# Power_Stage.net
KiCad netlist of a schematic drawn in Altium Designer
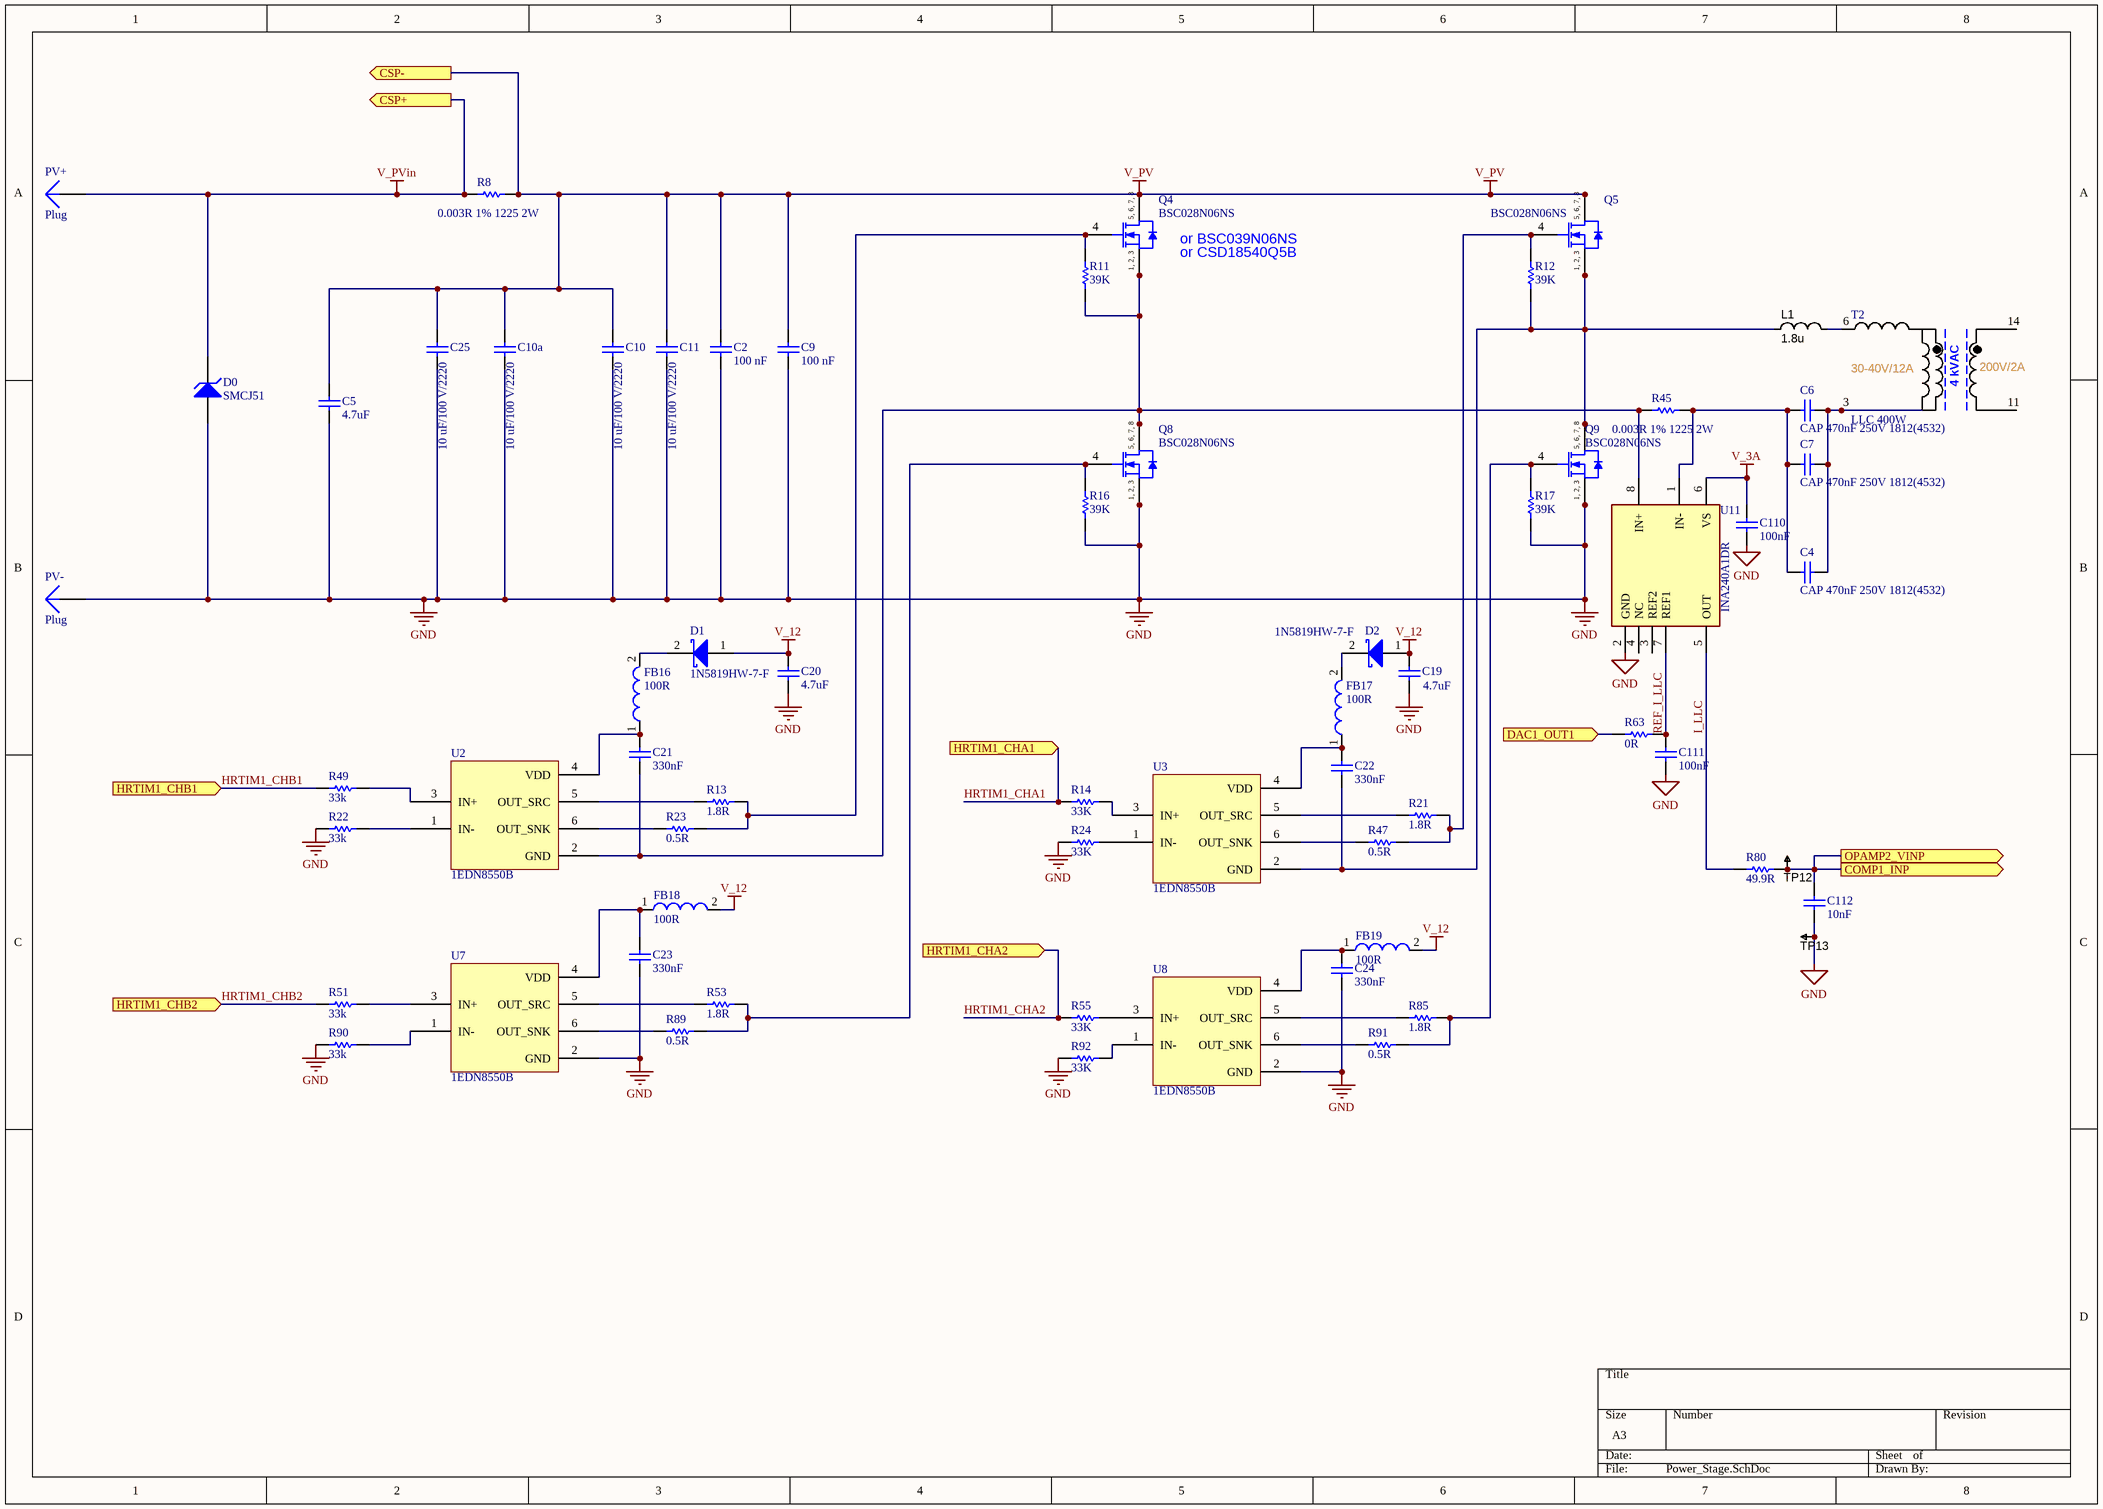
[diagram p0: Power_Stage.SchDoc]

(export (version "E")
  (design (tool "Eeschema 10.0.6"))
  (components
    (comp (ref "C2")
      (value "100 nF")
      (footprint "CAPC2013X94X50NL20T25")
      (description "X7R 100nF ±10% 100V 0805 Multilayer Ceramic Capacitors MLCC - SMD/SMT ROHS")
      (fields
        (field (name "MANUFACTURER") "AVX Interconnect / Elco")
        (field (name "PART NUMBER") "08051C104JAT2A")
      )
      (libsource (lib "Altium Content Vault") (part "CAP"))
    )
    (comp (ref "C4")
      (value "CAP 470nF 250V 1812(4532)")
      (footprint "CAPC1812(4532)190_M")
      (description "CAP 470nF 250V ±10% 1812 (4532 Metric) Thickness 1.9mm SMD")
      (fields (field (name "TOLERANCE") "Â±10%"))
      (libsource (lib "Altium Content Vault") (part "CAP"))
    )
    (comp (ref "C5")
      (value "4.7uF")
      (footprint "CAPC3225X279X50NL20T25")
      (description "Ceramic Capacitor, 100 V, 4.7 uF, +/-10%, -55 to 85 degC, 2-Pin SMD (1210), RoHS, Tape and Reel")
      (fields (field (name "TOLERANCE") "10%") (field (name "MANUFACTURER") "AVX"))
      (libsource (lib "DCDC") (part "CMP-2000-05478-1"))
    )
    (comp (ref "C6")
      (value "CAP 470nF 250V 1812(4532)")
      (footprint "CAPC1812(4532)190_M")
      (description "CAP 470nF 250V ±10% 1812 (4532 Metric) Thickness 1.9mm SMD")
      (fields (field (name "TOLERANCE") "Â±10%"))
      (libsource (lib "Altium Content Vault") (part "CAP"))
    )
    (comp (ref "C7")
      (value "CAP 470nF 250V 1812(4532)")
      (footprint "CAPC1812(4532)190_M")
      (description "CAP 470nF 250V ±10% 1812 (4532 Metric) Thickness 1.9mm SMD")
      (fields (field (name "TOLERANCE") "Â±10%"))
      (libsource (lib "Altium Content Vault") (part "CAP"))
    )
    (comp (ref "C9")
      (value "100 nF")
      (footprint "CAPC2013X94X50NL20T25")
      (description "X7R 100nF ±10% 100V 0805 Multilayer Ceramic Capacitors MLCC - SMD/SMT ROHS")
      (fields
        (field (name "MANUFACTURER") "AVX Interconnect / Elco")
        (field (name "PART NUMBER") "08051C104JAT2A")
      )
      (libsource (lib "Altium Content Vault") (part "CAP"))
    )
    (comp (ref "C10")
      (value "10 uF/100 V/2220")
      (footprint "CAPC5750X279X64LL40T39")
      (description "Chip Capacitor, 10 uF, +/- 20%, 100 V, -55 to 125 degC, 2220 (5750 Metric), RoHS, Tape and Reel")
      (fields (field (name "MANUFACTURER") "AVX") (field (name "MANUFACTURER PART NUMBER") "22201C106MAT2A"))
      (libsource (lib "Altium Content Vault") (part "CAP-NP-2"))
    )
    (comp (ref "C10a")
      (value "10 uF/100 V/2220")
      (footprint "CAPC5750X279X64LL40T39")
      (description "Chip Capacitor, 10 uF, +/- 20%, 100 V, -55 to 125 degC, 2220 (5750 Metric), RoHS, Tape and Reel")
      (fields (field (name "MANUFACTURER") "AVX") (field (name "MANUFACTURER PART NUMBER") "22201C106MAT2A"))
      (libsource (lib "Altium Content Vault") (part "CAP-NP-2"))
    )
    (comp (ref "C11")
      (value "10 uF/100 V/2220")
      (footprint "CAPC5750X279X64LL40T39")
      (description "Chip Capacitor, 10 uF, +/- 20%, 100 V, -55 to 125 degC, 2220 (5750 Metric), RoHS, Tape and Reel")
      (fields (field (name "MANUFACTURER") "AVX") (field (name "MANUFACTURER PART NUMBER") "22201C106MAT2A"))
      (libsource (lib "Altium Content Vault") (part "CAP-NP-2"))
    )
    (comp (ref "C19")
      (value "C1206C105K3RACTU")
      (footprint "CAPC3216X180X50ML20T25")
      (description "X7R ±10% 50V 4.7uF 1206 Multilayer Ceramic Capacitors MLCC - SMD/SMT ROHS")
      (fields
        (field (name "CAPACITANCE") "4.7uF")
        (field (name "MANUFACTURER") "Kemet")
        (field (name "TOLERANCE") "10%")
      )
      (libsource (lib "Altium Content Vault") (part "CAP-NP-2"))
    )
    (comp (ref "C20")
      (value "C1206C105K3RACTU")
      (footprint "CAPC3216X180X50ML20T25")
      (description "X7R ±10% 50V 4.7uF 1206 Multilayer Ceramic Capacitors MLCC - SMD/SMT ROHS")
      (fields
        (field (name "CAPACITANCE") "4.7uF")
        (field (name "MANUFACTURER") "Kemet")
        (field (name "TOLERANCE") "10%")
      )
      (libsource (lib "Altium Content Vault") (part "CAP-NP-2"))
    )
    (comp (ref "C21")
      (value "330nF")
      (footprint "CAPC2013X135X45ML10T25")
      (description "X7R ±10% 50V 330nF 0805 Multilayer Ceramic Capacitors MLCC - SMD/SMT ROHS")
      (fields (field (name "VOLTAGE") "50V") (field (name "TOLERANCE") "10%"))
      (libsource (lib "Altium Content Vault") (part "CAP-NP-2"))
    )
    (comp (ref "C22")
      (value "330nF")
      (footprint "CAPC2013X135X45ML10T25")
      (description "X7R ±10% 50V 330nF 0805 Multilayer Ceramic Capacitors MLCC - SMD/SMT ROHS")
      (fields (field (name "VOLTAGE") "50V") (field (name "TOLERANCE") "10%"))
      (libsource (lib "Altium Content Vault") (part "CAP-NP-2"))
    )
    (comp (ref "C23")
      (value "330nF")
      (footprint "CAPC2013X135X45ML10T25")
      (description "X7R ±10% 50V 330nF 0805 Multilayer Ceramic Capacitors MLCC - SMD/SMT ROHS")
      (fields (field (name "VOLTAGE") "50V") (field (name "TOLERANCE") "10%"))
      (libsource (lib "Altium Content Vault") (part "CAP-NP-2"))
    )
    (comp (ref "C24")
      (value "330nF")
      (footprint "CAPC2013X135X45ML10T25")
      (description "X7R ±10% 50V 330nF 0805 Multilayer Ceramic Capacitors MLCC - SMD/SMT ROHS")
      (fields (field (name "VOLTAGE") "50V") (field (name "TOLERANCE") "10%"))
      (libsource (lib "Altium Content Vault") (part "CAP-NP-2"))
    )
    (comp (ref "C25")
      (value "10 uF/100 V/2220")
      (footprint "CAPC5750X279X64LL40T39")
      (description "Chip Capacitor, 10 uF, +/- 20%, 100 V, -55 to 125 degC, 2220 (5750 Metric), RoHS, Tape and Reel")
      (fields (field (name "MANUFACTURER") "AVX") (field (name "MANUFACTURER PART NUMBER") "22201C106MAT2A"))
      (libsource (lib "Altium Content Vault") (part "CAP-NP-2"))
    )
    (comp (ref "C110")
      (value "100nF")
      (footprint "CAPC1608X90X35NL10T15")
      (description "X7R 100nF ±10% 50V 0603 Multilayer Ceramic Capacitors MLCC - SMD/SMT ROHS")
      (fields (field (name "PART NUMBER") "GCM188R72A104KA64D") (field (name "MANUFACTURER") "Murata"))
      (libsource (lib "DCDC") (part "CAP"))
    )
    (comp (ref "C111")
      (value "100nF")
      (footprint "CAPC1608X90X35NL10T15")
      (description "X7R 100nF ±10% 50V 0603 Multilayer Ceramic Capacitors MLCC - SMD/SMT ROHS")
      (fields (field (name "PART NUMBER") "GCM188R72A104KA64D") (field (name "MANUFACTURER") "Murata"))
      (libsource (lib "DCDC") (part "CAP"))
    )
    (comp (ref "C112")
      (value "10nF")
      (footprint "CAPC1005X56X25NL10T15")
      (description "X7R ±10% 50V 10nF 0603 Multilayer Ceramic Capacitors MLCC - SMD/SMT ROHS")
      (fields
        (field (name "MANUFACTURER") "AVX Interconnect / Elco")
        (field (name "PART NUMBER") "04023C103JAT2A")
      )
      (libsource (lib "DCDC") (part "CAP"))
    )
    (comp (ref "D0")
      (value "SMCJ51")
      (footprint "FAIR-DO-214AB-2_V")
      (description "Transient Voltage Suppressor, 1500 W, 36 V, 2-Pin SMD, RoHS, Tape and Reel")
      (fields (field (name "MANUFACTURER") "Fairchild Semiconductor"))
      (libsource (lib "Altium Content Vault") (part "DZEN-AK-2"))
    )
    (comp (ref "D1")
      (value "1N5819HW-7-F")
      (footprint "DIOD-SOD-123-2_V")
      (fields (field (name "MANUFACTURER") "Diodes Inc") (field (name "JLCPCB PART #") "C8598"))
      (libsource (lib "Altium Content Vault") (part "DIOD-DSKY-A1K2-2"))
    )
    (comp (ref "D2")
      (value "1N5819HW-7-F")
      (footprint "DIOD-SOD-123-2_V")
      (fields (field (name "MANUFACTURER") "Diodes Inc") (field (name "JLCPCB PART #") "C8598"))
      (libsource (lib "Altium Content Vault") (part "DIOD-DSKY-A1K2-2"))
    )
    (comp (ref "FB16")
      (value "100R")
      (footprint "SMD-0603")
      (description "SMD EMI Suppression Ferrite Bead WE-CBF, Z = 1500 Ohm")
      (libsource (lib "Altium Content Vault") (part "PAS-IND-INDUCTOR-2"))
    )
    (comp (ref "FB17")
      (value "100R")
      (footprint "SMD-0603")
      (description "SMD EMI Suppression Ferrite Bead WE-CBF, Z = 1500 Ohm")
      (libsource (lib "Altium Content Vault") (part "PAS-IND-INDUCTOR-2"))
    )
    (comp (ref "FB18")
      (value "100R")
      (footprint "SMD-0603")
      (description "SMD EMI Suppression Ferrite Bead WE-CBF, Z = 1500 Ohm")
      (libsource (lib "Altium Content Vault") (part "PAS-IND-INDUCTOR-2"))
    )
    (comp (ref "FB19")
      (value "100R")
      (footprint "SMD-0603")
      (description "SMD EMI Suppression Ferrite Bead WE-CBF, Z = 1500 Ohm")
      (libsource (lib "Altium Content Vault") (part "PAS-IND-INDUCTOR-2"))
    )
    (comp (ref "L1")
      (value "1.8u")
      (footprint "IND LLC")
      (description "Inductor SMD chip 150nH 1008")
      (fields (field (name "TOLERANCE") "±5%"))
      (libsource (lib "PBL - Inductors") (part "INDC_150n_1008"))
    )
    (comp (ref "PV+")
      (value "Plug")
      (footprint "PV_PAD")
      (fields (field (name "PUBLISHER") "Altium Limited"))
      (libsource (lib "Miscellaneous Connectors") (part "Plug"))
    )
    (comp (ref "PV-")
      (value "Plug")
      (footprint "PV_PAD")
      (fields (field (name "PUBLISHER") "Altium Limited"))
      (libsource (lib "Miscellaneous Connectors") (part "Plug"))
    )
    (comp (ref "Q4")
      (value "BSC028N06NS")
      (footprint "INF-PG-TDSON-8-1_V")
      (description "N-Channel OptiMOS Power-Transistor, 60 V VDS, 100 A ID, -55 to 150 degC, PG-TDSON-8-1, Reel, Green")
      (fields (field (name "PARTNUMBER") "BSC027N06LS5") (field (name "MANUFACTURER") "Infineon"))
      (libsource (lib "Altium Content Vault") (part "INF-NEMOS-SSSGDDDD-8"))
    )
    (comp (ref "Q5")
      (value "BSC028N06NS")
      (footprint "INF-PG-TDSON-8-1_V")
      (description "N-Channel OptiMOS Power-Transistor, 60 V VDS, 100 A ID, -55 to 150 degC, PG-TDSON-8-1, Reel, Green")
      (fields (field (name "PARTNUMBER") "BSC027N06LS5") (field (name "MANUFACTURER") "Infineon"))
      (libsource (lib "Altium Content Vault") (part "INF-NEMOS-SSSGDDDD-8"))
    )
    (comp (ref "Q8")
      (value "BSC028N06NS")
      (footprint "INF-PG-TDSON-8-1_V")
      (description "N-Channel OptiMOS Power-Transistor, 60 V VDS, 100 A ID, -55 to 150 degC, PG-TDSON-8-1, Reel, Green")
      (fields (field (name "PARTNUMBER") "BSC027N06LS5") (field (name "MANUFACTURER") "Infineon"))
      (libsource (lib "Altium Content Vault") (part "INF-NEMOS-SSSGDDDD-8"))
    )
    (comp (ref "Q9")
      (value "BSC028N06NS")
      (footprint "INF-PG-TDSON-8-1_V")
      (description "N-Channel OptiMOS Power-Transistor, 60 V VDS, 100 A ID, -55 to 150 degC, PG-TDSON-8-1, Reel, Green")
      (fields (field (name "PARTNUMBER") "BSC027N06LS5") (field (name "MANUFACTURER") "Infineon"))
      (libsource (lib "Altium Content Vault") (part "INF-NEMOS-SSSGDDDD-8"))
    )
    (comp (ref "R8")
      (value "0.003R 1% 1225 2W")
      (footprint "RESC3264X06N")
      (description "RES SMD 3 MOHM 3W 2512 WIDE")
      (fields
        (field (name "MANUFACTURER") "Susumu")
        (field (name "MANUFACTURER PART NUMBER") "KRL6432E-M-R003-F-T1")
      )
      (libsource (lib "Miscellaneous Devices") (part "RES"))
    )
    (comp (ref "R11")
      (value "39K")
      (footprint "RESC1608X55X30NL20T10")
      (description "±1% 39kΩ ±100ppm/℃ 0.1W 0603 Chip Resistor - Surface Mount ROHS")
      (fields (field (name "PART NUMBER") "RK73B1JTTD103J") (field (name "MANUFACTURER") "KOA Speer"))
      (libsource (lib "Altium Content Vault") (part "RES"))
    )
    (comp (ref "R12")
      (value "39K")
      (footprint "RESC1608X55X30NL20T10")
      (description "±1% 39kΩ ±100ppm/℃ 0.1W 0603 Chip Resistor - Surface Mount ROHS")
      (fields (field (name "PART NUMBER") "RK73B1JTTD103J") (field (name "MANUFACTURER") "KOA Speer"))
      (libsource (lib "Altium Content Vault") (part "RES"))
    )
    (comp (ref "R13")
      (value "1.8R")
      (footprint "RESC3216X70X40ML20T20")
      (fields (field (name "MANUFACTURER") "KOA Speer") (field (name "PART NUMBER") "RK73B2BTTD4R7J"))
      (libsource (lib "Altium Content Vault") (part "RES"))
    )
    (comp (ref "R14")
      (value "33K")
      (footprint "RESC1608X55X25ML10T15")
      (description "Chip Resistor, 100 Ohm, +/- 1%, 0.1 W, -55 to 155 degC, 0603 (1608 Metric), RoHS, Tape and Reel")
      (fields (field (name "TOLERANCE") "1%") (field (name "MANUFACTURER") "Yageo"))
      (libsource (lib "Altium Content Vault") (part "RES-2"))
    )
    (comp (ref "R16")
      (value "39K")
      (footprint "RESC1608X55X30NL20T10")
      (description "±1% 39kΩ ±100ppm/℃ 0.1W 0603 Chip Resistor - Surface Mount ROHS")
      (fields (field (name "PART NUMBER") "RK73B1JTTD103J") (field (name "MANUFACTURER") "KOA Speer"))
      (libsource (lib "Altium Content Vault") (part "RES"))
    )
    (comp (ref "R17")
      (value "39K")
      (footprint "RESC1608X55X30NL20T10")
      (description "±1% 39kΩ ±100ppm/℃ 0.1W 0603 Chip Resistor - Surface Mount ROHS")
      (fields (field (name "PART NUMBER") "RK73B1JTTD103J") (field (name "MANUFACTURER") "KOA Speer"))
      (libsource (lib "Altium Content Vault") (part "RES"))
    )
    (comp (ref "R21")
      (value "1.8R")
      (footprint "RESC3216X70X40ML20T20")
      (fields (field (name "MANUFACTURER") "KOA Speer") (field (name "PART NUMBER") "RK73B2BTTD4R7J"))
      (libsource (lib "Altium Content Vault") (part "RES"))
    )
    (comp (ref "R22")
      (value "33k")
      (footprint "RESC1608X55X25ML10T15")
      (description "Chip Resistor, 100 Ohm, +/- 1%, 0.1 W, -55 to 155 degC, 0603 (1608 Metric), RoHS, Tape and Reel")
      (fields (field (name "TOLERANCE") "1%") (field (name "MANUFACTURER") "Yageo"))
      (libsource (lib "Altium Content Vault") (part "RES-2"))
    )
    (comp (ref "R23")
      (value "0.5R")
      (footprint "RESC3216X70X40ML20T20")
      (fields (field (name "MANUFACTURER") "KOA Speer") (field (name "PART NUMBER") "RK73B2BTTD4R7J"))
      (libsource (lib "Altium Content Vault") (part "RES"))
    )
    (comp (ref "R24")
      (value "33K")
      (footprint "RESC1608X55X25ML10T15")
      (description "Chip Resistor, 100 Ohm, +/- 1%, 0.1 W, -55 to 155 degC, 0603 (1608 Metric), RoHS, Tape and Reel")
      (fields (field (name "TOLERANCE") "1%") (field (name "MANUFACTURER") "Yageo"))
      (libsource (lib "Altium Content Vault") (part "RES-2"))
    )
    (comp (ref "R45")
      (value "0.003R 1% 1225 2W")
      (footprint "RESC3264X06N")
      (description "RES SMD 3 MOHM 3W 2512 WIDE")
      (fields
        (field (name "MANUFACTURER") "Susumu")
        (field (name "MANUFACTURER PART NUMBER") "KRL6432E-M-R003-F-T1")
      )
      (libsource (lib "Miscellaneous Devices") (part "RES"))
    )
    (comp (ref "R47")
      (value "0.5R")
      (footprint "RESC3216X70X40ML20T20")
      (fields (field (name "MANUFACTURER") "KOA Speer") (field (name "PART NUMBER") "RK73B2BTTD4R7J"))
      (libsource (lib "Altium Content Vault") (part "RES"))
    )
    (comp (ref "R49")
      (value "33k")
      (footprint "RESC1608X55X25ML10T15")
      (description "Chip Resistor, 100 Ohm, +/- 1%, 0.1 W, -55 to 155 degC, 0603 (1608 Metric), RoHS, Tape and Reel")
      (fields (field (name "TOLERANCE") "1%") (field (name "MANUFACTURER") "Yageo"))
      (libsource (lib "Altium Content Vault") (part "RES-2"))
    )
    (comp (ref "R51")
      (value "33k")
      (footprint "RESC1608X55X25ML10T15")
      (description "Chip Resistor, 100 Ohm, +/- 1%, 0.1 W, -55 to 155 degC, 0603 (1608 Metric), RoHS, Tape and Reel")
      (fields (field (name "TOLERANCE") "1%") (field (name "MANUFACTURER") "Yageo"))
      (libsource (lib "Altium Content Vault") (part "RES-2"))
    )
    (comp (ref "R53")
      (value "1.8R")
      (footprint "RESC3216X70X40ML20T20")
      (fields (field (name "MANUFACTURER") "KOA Speer") (field (name "PART NUMBER") "RK73B2BTTD4R7J"))
      (libsource (lib "Altium Content Vault") (part "RES"))
    )
    (comp (ref "R55")
      (value "33K")
      (footprint "RESC1608X55X25ML10T15")
      (description "Chip Resistor, 100 Ohm, +/- 1%, 0.1 W, -55 to 155 degC, 0603 (1608 Metric), RoHS, Tape and Reel")
      (fields (field (name "TOLERANCE") "1%") (field (name "MANUFACTURER") "Yageo"))
      (libsource (lib "Altium Content Vault") (part "RES-2"))
    )
    (comp (ref "R63")
      (value "0R")
      (footprint "RESC1608X55X25ML10T15")
      (description "±1% 0Ω 0.1W 0603 Chip Resistor - Surface Mount ROHS")
      (fields (field (name "TOLERANCE") "5%") (field (name "MANUFACTURER") "Yageo"))
      (libsource (lib "Altium Content Vault") (part "RES-2"))
    )
    (comp (ref "R80")
      (value "49.9R")
      (footprint "RESC1608X55X30ML15T15")
      (description "±1% ±200ppm/℃ 0.1W 49.9Ω 0603 Chip Resistor - Surface Mount ROHS")
      (fields (field (name "MANUFACTURER") "Panasonic") (field (name "PART NUMBER") "ERJ-3EKF49R9V"))
      (libsource (lib "Altium Content Vault") (part "RES"))
    )
    (comp (ref "R85")
      (value "1.8R")
      (footprint "RESC3216X70X40ML20T20")
      (fields (field (name "MANUFACTURER") "KOA Speer") (field (name "PART NUMBER") "RK73B2BTTD4R7J"))
      (libsource (lib "Altium Content Vault") (part "RES"))
    )
    (comp (ref "R89")
      (value "0.5R")
      (footprint "RESC3216X70X40ML20T20")
      (fields (field (name "MANUFACTURER") "KOA Speer") (field (name "PART NUMBER") "RK73B2BTTD4R7J"))
      (libsource (lib "Altium Content Vault") (part "RES"))
    )
    (comp (ref "R90")
      (value "33k")
      (footprint "RESC1608X55X25ML10T15")
      (description "Chip Resistor, 100 Ohm, +/- 1%, 0.1 W, -55 to 155 degC, 0603 (1608 Metric), RoHS, Tape and Reel")
      (fields (field (name "TOLERANCE") "1%") (field (name "MANUFACTURER") "Yageo"))
      (libsource (lib "Altium Content Vault") (part "RES-2"))
    )
    (comp (ref "R91")
      (value "0.5R")
      (footprint "RESC3216X70X40ML20T20")
      (fields (field (name "MANUFACTURER") "KOA Speer") (field (name "PART NUMBER") "RK73B2BTTD4R7J"))
      (libsource (lib "Altium Content Vault") (part "RES"))
    )
    (comp (ref "R92")
      (value "33K")
      (footprint "RESC1608X55X25ML10T15")
      (description "Chip Resistor, 100 Ohm, +/- 1%, 0.1 W, -55 to 155 degC, 0603 (1608 Metric), RoHS, Tape and Reel")
      (fields (field (name "TOLERANCE") "1%") (field (name "MANUFACTURER") "Yageo"))
      (libsource (lib "Altium Content Vault") (part "RES-2"))
    )
    (comp (ref "T2")
      (value "LLC 400W")
      (footprint "ETD39-K-V-16P-HORIZONTAL-PRI")
      (description "Lr=1.9uH\r\nLm=10.2uH\r\nn=5.7\r\nVin=30-40V\r\nVout=200V")
      (libsource (lib "TI-ETD39-200V-2A-LLC") (part "TI-ETD39-200V-2A-LLC"))
    )
    (comp (ref "TP12")
      (value "TESTPOINT")
      (footprint "TP-R60")
      (description "SMD test pin")
      (libsource (lib "PBL - Test Points") (part "TESTPOINT"))
    )
    (comp (ref "TP13")
      (value "TESTPOINT")
      (footprint "TP-R60")
      (description "SMD test pin")
      (libsource (lib "PBL - Test Points") (part "TESTPOINT"))
    )
    (comp (ref "U2")
      (value "1EDN8550B")
      (footprint "SOT23-6")
      (description "Single-channel EiceDRIVER™ with true  differential inputs")
      (libsource (lib "1EDN8550B") (part "1EDN8550B"))
    )
    (comp (ref "U3")
      (value "1EDN8550B")
      (footprint "SOT23-6")
      (description "Single-channel EiceDRIVER™ with true  differential inputs")
      (libsource (lib "1EDN8550B") (part "1EDN8550B"))
    )
    (comp (ref "U7")
      (value "1EDN8550B")
      (footprint "SOT23-6")
      (description "Single-channel EiceDRIVER™ with true  differential inputs")
      (libsource (lib "1EDN8550B") (part "1EDN8550B"))
    )
    (comp (ref "U8")
      (value "1EDN8550B")
      (footprint "SOT23-6")
      (description "Single-channel EiceDRIVER™ with true  differential inputs")
      (libsource (lib "1EDN8550B") (part "1EDN8550B"))
    )
    (comp (ref "U11")
      (value "INA240A1DR")
      (footprint "SOIC127P600X175-8AN")
      (description "IC CURR SENSE 1 CIRCUIT 8SOIC")
      (libsource (lib "PBL - Integrated Circuits") (part "a9db4a8a3d73c22b64f8e8a0c239388"))
    )
  )
  (nets
    (net (code "1") (name "/COMP1_INP") (class "Default")
      (node (ref "C112") (pin "2") (pinfunction "2_2") (pintype "passive"))
      (node (ref "R80") (pin "2") (pinfunction "2_2") (pintype "passive"))
      (node (ref "TP12") (pin "1") (pintype "passive"))
    )
    (net (code "2") (name "/DAC1_OUT1") (class "Default")
      (node (ref "R63") (pin "1") (pinfunction "1_1") (pintype "passive"))
    )
    (net (code "3") (name "/HRTIM1_CHA1") (class "Default")
      (node (ref "R14") (pin "1") (pinfunction "1_1") (pintype "passive"))
    )
    (net (code "4") (name "/HRTIM1_CHA2") (class "Default")
      (node (ref "R55") (pin "1") (pinfunction "1_1") (pintype "passive"))
    )
    (net (code "5") (name "/HRTIM1_CHB1") (class "Default")
      (node (ref "R49") (pin "1") (pinfunction "1_1") (pintype "passive"))
    )
    (net (code "6") (name "/HRTIM1_CHB2") (class "Default")
      (node (ref "R51") (pin "1") (pinfunction "1_1") (pintype "passive"))
    )
    (net (code "7") (name "/I_LLC") (class "Default")
      (node (ref "R80") (pin "1") (pinfunction "1_1") (pintype "passive"))
      (node (ref "U11") (pin "5") (pinfunction "OUT_5") (pintype "passive"))
    )
    (net (code "8") (name "/REF_I_LLC") (class "Default")
      (node (ref "C111") (pin "2") (pinfunction "2_2") (pintype "passive"))
      (node (ref "R63") (pin "2") (pinfunction "2_2") (pintype "passive"))
      (node (ref "U11") (pin "7") (pinfunction "REF1_7") (pintype "passive"))
    )
    (net (code "9") (name "GND") (class "Default")
      (node (ref "C10") (pin "1") (pinfunction "1_1") (pintype "passive"))
      (node (ref "C10a") (pin "1") (pinfunction "1_1") (pintype "passive"))
      (node (ref "C11") (pin "1") (pinfunction "1_1") (pintype "passive"))
      (node (ref "C110") (pin "1") (pinfunction "1_1") (pintype "passive"))
      (node (ref "C111") (pin "1") (pinfunction "1_1") (pintype "passive"))
      (node (ref "C112") (pin "1") (pinfunction "1_1") (pintype "passive"))
      (node (ref "C19") (pin "1") (pinfunction "1_1") (pintype "passive"))
      (node (ref "C2") (pin "1") (pinfunction "1_1") (pintype "passive"))
      (node (ref "C20") (pin "1") (pinfunction "1_1") (pintype "passive"))
      (node (ref "C23") (pin "1") (pinfunction "1_1") (pintype "passive"))
      (node (ref "C24") (pin "1") (pinfunction "1_1") (pintype "passive"))
      (node (ref "C25") (pin "1") (pinfunction "1_1") (pintype "passive"))
      (node (ref "C5") (pin "1") (pinfunction "1_1") (pintype "passive"))
      (node (ref "C9") (pin "1") (pinfunction "1_1") (pintype "passive"))
      (node (ref "D0") (pin "1") (pinfunction "A_1") (pintype "passive"))
      (node (ref "PV-") (pin "1") (pinfunction "1_1") (pintype "passive"))
      (node (ref "Q8") (pin "1") (pinfunction "SOURCE_1") (pintype "passive"))
      (node (ref "Q8") (pin "2") (pinfunction "SOURCE_2") (pintype "passive"))
      (node (ref "Q8") (pin "3") (pinfunction "SOURCE_3") (pintype "passive"))
      (node (ref "Q9") (pin "1") (pinfunction "SOURCE_1") (pintype "passive"))
      (node (ref "Q9") (pin "2") (pinfunction "SOURCE_2") (pintype "passive"))
      (node (ref "Q9") (pin "3") (pinfunction "SOURCE_3") (pintype "passive"))
      (node (ref "R16") (pin "1") (pinfunction "1_1") (pintype "passive"))
      (node (ref "R17") (pin "1") (pinfunction "1_1") (pintype "passive"))
      (node (ref "R22") (pin "1") (pinfunction "1_1") (pintype "passive"))
      (node (ref "R24") (pin "1") (pinfunction "1_1") (pintype "passive"))
      (node (ref "R90") (pin "1") (pinfunction "1_1") (pintype "passive"))
      (node (ref "R92") (pin "1") (pinfunction "1_1") (pintype "passive"))
      (node (ref "TP13") (pin "1") (pintype "passive"))
      (node (ref "U11") (pin "2") (pinfunction "GND_2") (pintype "power_in"))
      (node (ref "U7") (pin "2") (pinfunction "GND_2") (pintype "passive"))
      (node (ref "U8") (pin "2") (pinfunction "GND_2") (pintype "passive"))
    )
    (net (code "10") (name "Net-(C4-Pad2)") (class "Default")
      (node (ref "C4") (pin "2") (pinfunction "2_2") (pintype "passive"))
      (node (ref "C6") (pin "2") (pinfunction "2_2") (pintype "passive"))
      (node (ref "C7") (pin "2") (pinfunction "2_2") (pintype "passive"))
      (node (ref "T2") (pin "3") (pinfunction "3_3") (pintype "passive"))
    )
    (net (code "11") (name "Net-(D1-K)") (class "Default")
      (node (ref "D1") (pin "2") (pinfunction "K_2") (pintype "passive"))
      (node (ref "FB16") (pin "2") (pinfunction "2_2") (pintype "passive"))
    )
    (net (code "12") (name "Net-(D2-K)") (class "Default")
      (node (ref "D2") (pin "2") (pinfunction "K_2") (pintype "passive"))
      (node (ref "FB17") (pin "2") (pinfunction "2_2") (pintype "passive"))
    )
    (net (code "13") (name "Net-(L1-Pad2)") (class "Default")
      (node (ref "L1") (pin "2") (pinfunction "2_2") (pintype "passive"))
      (node (ref "T2") (pin "6") (pinfunction "6_6") (pintype "passive"))
    )
    (net (code "14") (name "Net-(Q4-GATE)") (class "Default")
      (node (ref "Q4") (pin "4") (pinfunction "GATE_4") (pintype "passive"))
      (node (ref "R11") (pin "2") (pinfunction "2_2") (pintype "passive"))
      (node (ref "R13") (pin "2") (pinfunction "2_2") (pintype "passive"))
      (node (ref "R23") (pin "2") (pinfunction "2_2") (pintype "passive"))
    )
    (net (code "15") (name "Net-(Q5-GATE)") (class "Default")
      (node (ref "Q5") (pin "4") (pinfunction "GATE_4") (pintype "passive"))
      (node (ref "R12") (pin "2") (pinfunction "2_2") (pintype "passive"))
      (node (ref "R21") (pin "2") (pinfunction "2_2") (pintype "passive"))
      (node (ref "R47") (pin "2") (pinfunction "2_2") (pintype "passive"))
    )
    (net (code "16") (name "Net-(Q8-GATE)") (class "Default")
      (node (ref "Q8") (pin "4") (pinfunction "GATE_4") (pintype "passive"))
      (node (ref "R16") (pin "2") (pinfunction "2_2") (pintype "passive"))
      (node (ref "R53") (pin "2") (pinfunction "2_2") (pintype "passive"))
      (node (ref "R89") (pin "2") (pinfunction "2_2") (pintype "passive"))
    )
    (net (code "17") (name "Net-(Q9-GATE)") (class "Default")
      (node (ref "Q9") (pin "4") (pinfunction "GATE_4") (pintype "passive"))
      (node (ref "R17") (pin "2") (pinfunction "2_2") (pintype "passive"))
      (node (ref "R85") (pin "2") (pinfunction "2_2") (pintype "passive"))
      (node (ref "R91") (pin "2") (pinfunction "2_2") (pintype "passive"))
    )
    (net (code "18") (name "Net-(U2-IN+)") (class "Default")
      (node (ref "R49") (pin "2") (pinfunction "2_2") (pintype "passive"))
      (node (ref "U2") (pin "3") (pinfunction "IN+_3") (pintype "passive"))
    )
    (net (code "19") (name "Net-(U2-IN-)") (class "Default")
      (node (ref "R22") (pin "2") (pinfunction "2_2") (pintype "passive"))
      (node (ref "U2") (pin "1") (pinfunction "IN-_1") (pintype "passive"))
    )
    (net (code "20") (name "Net-(U2-OUT_SNK)") (class "Default")
      (node (ref "R23") (pin "1") (pinfunction "1_1") (pintype "passive"))
      (node (ref "U2") (pin "6") (pinfunction "OUT_SNK_6") (pintype "passive"))
    )
    (net (code "21") (name "Net-(U2-OUT_SRC)") (class "Default")
      (node (ref "R13") (pin "1") (pinfunction "1_1") (pintype "passive"))
      (node (ref "U2") (pin "5") (pinfunction "OUT_SRC_5") (pintype "passive"))
    )
    (net (code "22") (name "Net-(U2-VDD)") (class "Default")
      (node (ref "C21") (pin "2") (pinfunction "2_2") (pintype "passive"))
      (node (ref "FB16") (pin "1") (pinfunction "1_1") (pintype "passive"))
      (node (ref "U2") (pin "4") (pinfunction "VDD_4") (pintype "passive"))
    )
    (net (code "23") (name "Net-(U3-GND)") (class "Default")
      (node (ref "C22") (pin "1") (pinfunction "1_1") (pintype "passive"))
      (node (ref "L1") (pin "1") (pinfunction "1_1") (pintype "passive"))
      (node (ref "Q5") (pin "1") (pinfunction "SOURCE_1") (pintype "passive"))
      (node (ref "Q5") (pin "2") (pinfunction "SOURCE_2") (pintype "passive"))
      (node (ref "Q5") (pin "3") (pinfunction "SOURCE_3") (pintype "passive"))
      (node (ref "Q9") (pin "5") (pinfunction "DRAIN_5") (pintype "passive"))
      (node (ref "Q9") (pin "6") (pinfunction "DRAIN_6") (pintype "passive"))
      (node (ref "Q9") (pin "7") (pinfunction "DRAIN_7") (pintype "passive"))
      (node (ref "Q9") (pin "8") (pinfunction "DRAIN_8") (pintype "passive"))
      (node (ref "R12") (pin "1") (pinfunction "1_1") (pintype "passive"))
      (node (ref "U3") (pin "2") (pinfunction "GND_2") (pintype "passive"))
    )
    (net (code "24") (name "Net-(U3-IN+)") (class "Default")
      (node (ref "R14") (pin "2") (pinfunction "2_2") (pintype "passive"))
      (node (ref "U3") (pin "3") (pinfunction "IN+_3") (pintype "passive"))
    )
    (net (code "25") (name "Net-(U3-IN-)") (class "Default")
      (node (ref "R24") (pin "2") (pinfunction "2_2") (pintype "passive"))
      (node (ref "U3") (pin "1") (pinfunction "IN-_1") (pintype "passive"))
    )
    (net (code "26") (name "Net-(U3-OUT_SNK)") (class "Default")
      (node (ref "R47") (pin "1") (pinfunction "1_1") (pintype "passive"))
      (node (ref "U3") (pin "6") (pinfunction "OUT_SNK_6") (pintype "passive"))
    )
    (net (code "27") (name "Net-(U3-OUT_SRC)") (class "Default")
      (node (ref "R21") (pin "1") (pinfunction "1_1") (pintype "passive"))
      (node (ref "U3") (pin "5") (pinfunction "OUT_SRC_5") (pintype "passive"))
    )
    (net (code "28") (name "Net-(U3-VDD)") (class "Default")
      (node (ref "C22") (pin "2") (pinfunction "2_2") (pintype "passive"))
      (node (ref "FB17") (pin "1") (pinfunction "1_1") (pintype "passive"))
      (node (ref "U3") (pin "4") (pinfunction "VDD_4") (pintype "passive"))
    )
    (net (code "29") (name "Net-(U7-IN+)") (class "Default")
      (node (ref "R51") (pin "2") (pinfunction "2_2") (pintype "passive"))
      (node (ref "U7") (pin "3") (pinfunction "IN+_3") (pintype "passive"))
    )
    (net (code "30") (name "Net-(U7-IN-)") (class "Default")
      (node (ref "R90") (pin "2") (pinfunction "2_2") (pintype "passive"))
      (node (ref "U7") (pin "1") (pinfunction "IN-_1") (pintype "passive"))
    )
    (net (code "31") (name "Net-(U7-OUT_SNK)") (class "Default")
      (node (ref "R89") (pin "1") (pinfunction "1_1") (pintype "passive"))
      (node (ref "U7") (pin "6") (pinfunction "OUT_SNK_6") (pintype "passive"))
    )
    (net (code "32") (name "Net-(U7-OUT_SRC)") (class "Default")
      (node (ref "R53") (pin "1") (pinfunction "1_1") (pintype "passive"))
      (node (ref "U7") (pin "5") (pinfunction "OUT_SRC_5") (pintype "passive"))
    )
    (net (code "33") (name "Net-(U7-VDD)") (class "Default")
      (node (ref "C23") (pin "2") (pinfunction "2_2") (pintype "passive"))
      (node (ref "FB18") (pin "1") (pinfunction "1_1") (pintype "passive"))
      (node (ref "U7") (pin "4") (pinfunction "VDD_4") (pintype "passive"))
    )
    (net (code "34") (name "Net-(U8-IN+)") (class "Default")
      (node (ref "R55") (pin "2") (pinfunction "2_2") (pintype "passive"))
      (node (ref "U8") (pin "3") (pinfunction "IN+_3") (pintype "passive"))
    )
    (net (code "35") (name "Net-(U8-IN-)") (class "Default")
      (node (ref "R92") (pin "2") (pinfunction "2_2") (pintype "passive"))
      (node (ref "U8") (pin "1") (pinfunction "IN-_1") (pintype "passive"))
    )
    (net (code "36") (name "Net-(U8-OUT_SNK)") (class "Default")
      (node (ref "R91") (pin "1") (pinfunction "1_1") (pintype "passive"))
      (node (ref "U8") (pin "6") (pinfunction "OUT_SNK_6") (pintype "passive"))
    )
    (net (code "37") (name "Net-(U8-OUT_SRC)") (class "Default")
      (node (ref "R85") (pin "1") (pinfunction "1_1") (pintype "passive"))
      (node (ref "U8") (pin "5") (pinfunction "OUT_SRC_5") (pintype "passive"))
    )
    (net (code "38") (name "Net-(U8-VDD)") (class "Default")
      (node (ref "C24") (pin "2") (pinfunction "2_2") (pintype "passive"))
      (node (ref "FB19") (pin "1") (pinfunction "1_1") (pintype "passive"))
      (node (ref "U8") (pin "4") (pinfunction "VDD_4") (pintype "passive"))
    )
    (net (code "39") (name "Net-(U11-IN+)") (class "Default")
      (node (ref "C21") (pin "1") (pinfunction "1_1") (pintype "passive"))
      (node (ref "Q4") (pin "1") (pinfunction "SOURCE_1") (pintype "passive"))
      (node (ref "Q4") (pin "2") (pinfunction "SOURCE_2") (pintype "passive"))
      (node (ref "Q4") (pin "3") (pinfunction "SOURCE_3") (pintype "passive"))
      (node (ref "Q8") (pin "5") (pinfunction "DRAIN_5") (pintype "passive"))
      (node (ref "Q8") (pin "6") (pinfunction "DRAIN_6") (pintype "passive"))
      (node (ref "Q8") (pin "7") (pinfunction "DRAIN_7") (pintype "passive"))
      (node (ref "Q8") (pin "8") (pinfunction "DRAIN_8") (pintype "passive"))
      (node (ref "R11") (pin "1") (pinfunction "1_1") (pintype "passive"))
      (node (ref "R45") (pin "1") (pinfunction "1_1") (pintype "passive"))
      (node (ref "U11") (pin "8") (pinfunction "IN+_8") (pintype "tri_state"))
      (node (ref "U2") (pin "2") (pinfunction "GND_2") (pintype "passive"))
    )
    (net (code "40") (name "Net-(U11-IN-)") (class "Default")
      (node (ref "C4") (pin "1") (pinfunction "1_1") (pintype "passive"))
      (node (ref "C6") (pin "1") (pinfunction "1_1") (pintype "passive"))
      (node (ref "C7") (pin "1") (pinfunction "1_1") (pintype "passive"))
      (node (ref "R45") (pin "2") (pinfunction "2_2") (pintype "passive"))
      (node (ref "U11") (pin "1") (pinfunction "IN-_1") (pintype "tri_state"))
    )
    (net (code "41") (name "V_3A") (class "Default")
      (node (ref "C110") (pin "2") (pinfunction "2_2") (pintype "passive"))
      (node (ref "U11") (pin "6") (pinfunction "VS_6") (pintype "power_in"))
    )
    (net (code "42") (name "V_12") (class "Default")
      (node (ref "C19") (pin "2") (pinfunction "2_2") (pintype "passive"))
      (node (ref "C20") (pin "2") (pinfunction "2_2") (pintype "passive"))
      (node (ref "D1") (pin "1") (pinfunction "A_1") (pintype "passive"))
      (node (ref "D2") (pin "1") (pinfunction "A_1") (pintype "passive"))
      (node (ref "FB18") (pin "2") (pinfunction "2_2") (pintype "passive"))
      (node (ref "FB19") (pin "2") (pinfunction "2_2") (pintype "passive"))
    )
    (net (code "43") (name "V_PV") (class "Default")
      (node (ref "C10") (pin "2") (pinfunction "2_2") (pintype "passive"))
      (node (ref "C10a") (pin "2") (pinfunction "2_2") (pintype "passive"))
      (node (ref "C11") (pin "2") (pinfunction "2_2") (pintype "passive"))
      (node (ref "C2") (pin "2") (pinfunction "2_2") (pintype "passive"))
      (node (ref "C25") (pin "2") (pinfunction "2_2") (pintype "passive"))
      (node (ref "C5") (pin "2") (pinfunction "2_2") (pintype "passive"))
      (node (ref "C9") (pin "2") (pinfunction "2_2") (pintype "passive"))
      (node (ref "Q4") (pin "5") (pinfunction "DRAIN_5") (pintype "passive"))
      (node (ref "Q4") (pin "6") (pinfunction "DRAIN_6") (pintype "passive"))
      (node (ref "Q4") (pin "7") (pinfunction "DRAIN_7") (pintype "passive"))
      (node (ref "Q4") (pin "8") (pinfunction "DRAIN_8") (pintype "passive"))
      (node (ref "Q5") (pin "5") (pinfunction "DRAIN_5") (pintype "passive"))
      (node (ref "Q5") (pin "6") (pinfunction "DRAIN_6") (pintype "passive"))
      (node (ref "Q5") (pin "7") (pinfunction "DRAIN_7") (pintype "passive"))
      (node (ref "Q5") (pin "8") (pinfunction "DRAIN_8") (pintype "passive"))
      (node (ref "R8") (pin "2") (pinfunction "2_2") (pintype "passive"))
    )
    (net (code "44") (name "V_PVin") (class "Default")
      (node (ref "D0") (pin "2") (pinfunction "K_2") (pintype "passive"))
      (node (ref "PV+") (pin "1") (pinfunction "1_1") (pintype "passive"))
      (node (ref "R8") (pin "1") (pinfunction "1_1") (pintype "passive"))
    )
    (net (code "45") (name "unconnected-(T2-Pad11)") (class "Default")
      (node (ref "T2") (pin "11") (pinfunction "11_11") (pintype "passive"))
    )
    (net (code "46") (name "unconnected-(T2-Pad14)") (class "Default")
      (node (ref "T2") (pin "14") (pinfunction "14_14") (pintype "passive"))
    )
    (net (code "47") (name "unconnected-(U11-NC-Pad4)") (class "Default")
      (node (ref "U11") (pin "4") (pinfunction "NC_4") (pintype "passive"))
    )
    (net (code "48") (name "unconnected-(U11-REF2-Pad3)") (class "Default")
      (node (ref "U11") (pin "3") (pinfunction "REF2_3") (pintype "passive"))
    )
  )
)
